# Microcontroller.net
KiCad netlist of a schematic drawn in Altium Designer
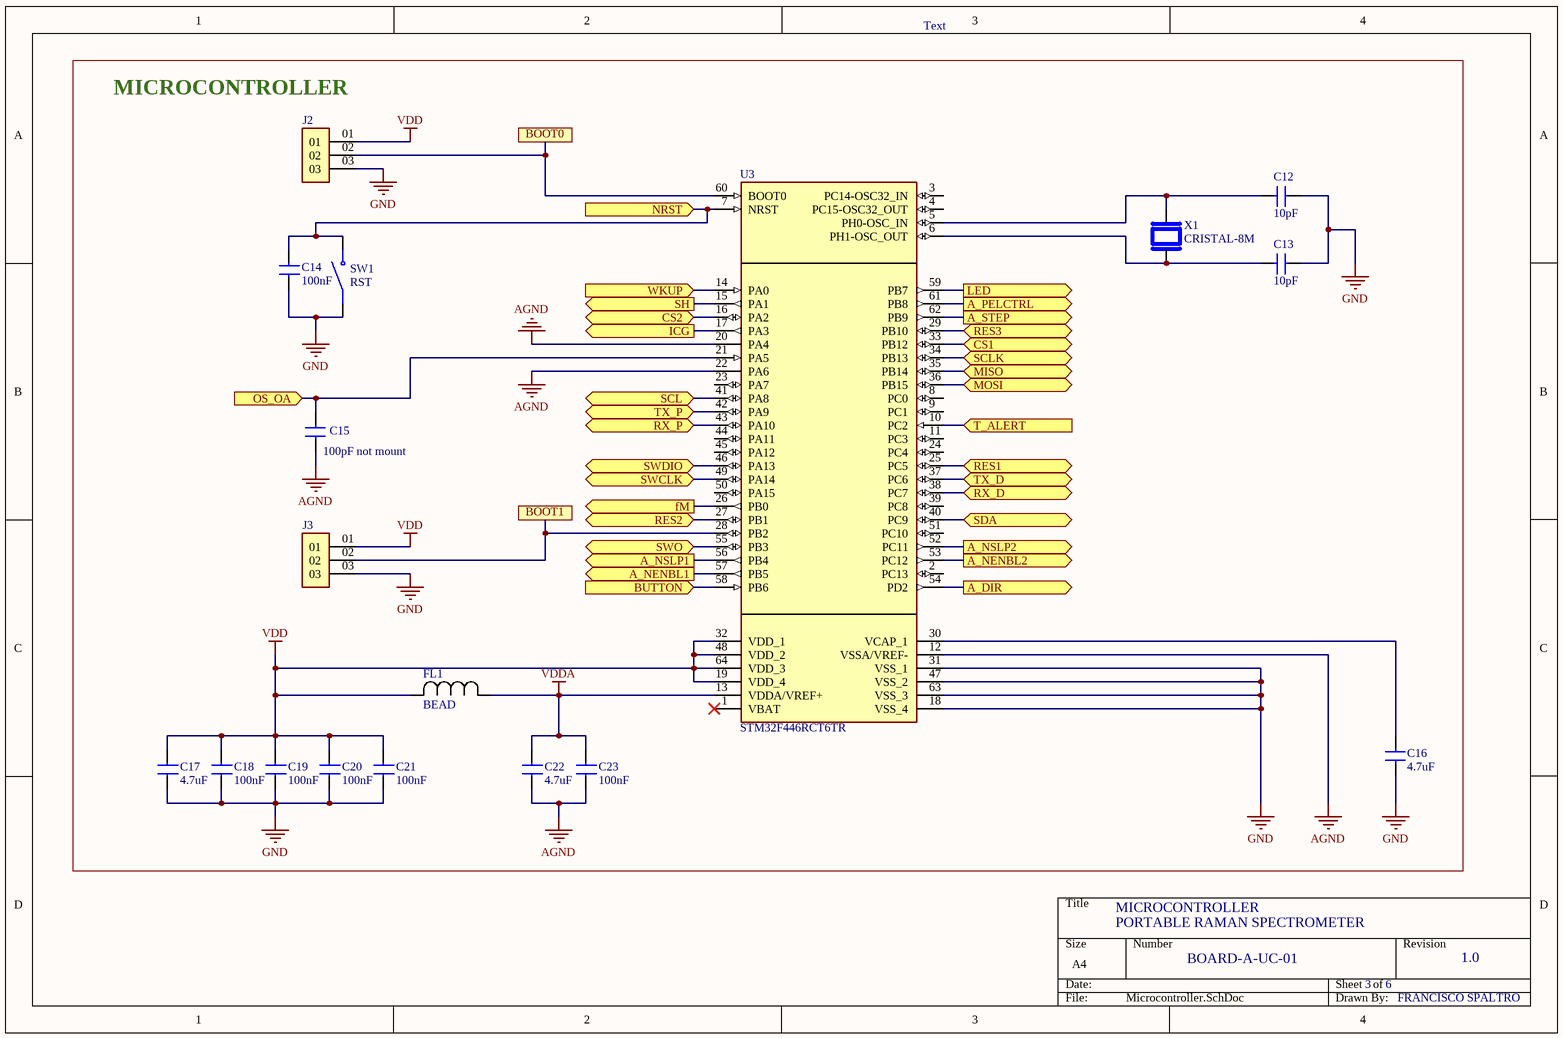
[diagram p0: Microcontroller.SchDoc]

(export (version "E")
  (design (tool "Eeschema 10.0.6"))
  (components
    (comp (ref "C12")
      (value "10pF")
      (footprint "RES_0805")
      (description "Generic Capacitor")
      (libsource (lib "Components") (part "CAP_0805"))
    )
    (comp (ref "C13")
      (value "10pF")
      (footprint "RES_0805")
      (description "Generic Capacitor")
      (libsource (lib "Components") (part "CAP_0805"))
    )
    (comp (ref "C14")
      (value "100nF")
      (footprint "RES_0805")
      (description "Generic Capacitor")
      (libsource (lib "Components") (part "CAP_0805"))
    )
    (comp (ref "C15")
      (value "100pF not mount")
      (footprint "RES_0805")
      (description "Generic Capacitor")
      (libsource (lib "Components") (part "CAP_0805"))
    )
    (comp (ref "C16")
      (value "4.7uF")
      (footprint "RES_0805")
      (description "Generic Capacitor")
      (libsource (lib "Components") (part "CAP_0805"))
    )
    (comp (ref "C17")
      (value "4.7uF")
      (footprint "RES_0805")
      (description "Generic Capacitor")
      (libsource (lib "Components") (part "CAP_0805"))
    )
    (comp (ref "C18")
      (value "100nF")
      (footprint "RES_0805")
      (description "Generic Capacitor")
      (libsource (lib "Components") (part "CAP_0805"))
    )
    (comp (ref "C19")
      (value "100nF")
      (footprint "RES_0805")
      (description "Generic Capacitor")
      (libsource (lib "Components") (part "CAP_0805"))
    )
    (comp (ref "C20")
      (value "100nF")
      (footprint "RES_0805")
      (description "Generic Capacitor")
      (libsource (lib "Components") (part "CAP_0805"))
    )
    (comp (ref "C21")
      (value "100nF")
      (footprint "RES_0805")
      (description "Generic Capacitor")
      (libsource (lib "Components") (part "CAP_0805"))
    )
    (comp (ref "C22")
      (value "4.7uF")
      (footprint "RES_0805")
      (description "Generic Capacitor")
      (libsource (lib "Components") (part "CAP_0805"))
    )
    (comp (ref "C23")
      (value "100nF")
      (footprint "RES_0805")
      (description "Generic Capacitor")
      (libsource (lib "Components") (part "CAP_0805"))
    )
    (comp (ref "FL1")
      (value "BEAD")
      (footprint "IND_1608_TDK-M")
      (description "INDUCTOR; SMT (0603); FERRITE-BEAD; 600; TOL=+/-25%; 0.5A; -55 DEGC TO +125 DEGC")
      (fields
        (field (name "MANUFACTURER_PART_NUMBER") "MMZ1608B601CTAH0")
        (field (name "COPYRIGHT") "Copyright (C) 2025 Ultra Librarian. All rights reserved.")
      )
      (libsource (lib "Components") (part "MMZ1608B601CTAH0"))
    )
    (comp (ref "J2")
      (value "PIN_HEADER_3")
      (footprint "GEN_PIN3")
      (description "Generic 40 mils drill size, 100 mils step")
      (fields (field (name "MF") "Samtec Inc.") (field (name "MP") "TS-103-T-A"))
      (libsource (lib "Components") (part "PIN_HEADER_3"))
    )
    (comp (ref "J3")
      (value "PIN_HEADER_3")
      (footprint "GEN_PIN3")
      (description "Generic 40 mils drill size, 100 mils step")
      (fields (field (name "MF") "Samtec Inc.") (field (name "MP") "TS-103-T-A"))
      (libsource (lib "Components") (part "PIN_HEADER_3"))
    )
    (comp (ref "SW1")
      (value "RST")
      (footprint "Components:SW_B3U-1000P")
      (description "Switch Tactile N.O. SPST Round Button Gull Wing 0.05A 12VDC 1.5N SMD Embossed T/R")
      (fields (field (name "MP") "B3U-1000P"))
      (libsource (lib "Components") (part "SW-B3U-1000P"))
    )
    (comp (ref "U3")
      (value "STM32F446RCT6TR")
      (footprint "QFP50P1200X1200X160-64N")
      (fields (field (name "MF") "STMicroelectronics"))
      (libsource (lib "CI") (part "STM32F446RCT6TR"))
    )
    (comp (ref "X1")
      (value "CRISTAL-8M")
      (footprint "XTALDFN320X250X100-2N")
      (description "8 MHz ±20ppm Crystal 8pF 500 Ohms 2-SMD, No Lead")
      (fields (field (name "MF") "NDK America, Inc.") (field (name "MP") "CG04874-8M"))
      (libsource (lib "CompPas") (part "CRISTAL-CG04874-8M"))
    )
  )
  (nets
    (net (code "1") (name "/A_DIR") (class "Default")
      (node (ref "U3") (pin "54") (pinfunction "PD2_54") (pintype "output"))
    )
    (net (code "2") (name "/A_NENBL1") (class "Default")
      (node (ref "U3") (pin "57") (pinfunction "PB5_57") (pintype "output"))
    )
    (net (code "3") (name "/A_NENBL2") (class "Default")
      (node (ref "U3") (pin "53") (pinfunction "PC12_53") (pintype "output"))
    )
    (net (code "4") (name "/A_NSLP1") (class "Default")
      (node (ref "U3") (pin "56") (pinfunction "PB4_56") (pintype "output"))
    )
    (net (code "5") (name "/A_NSLP2") (class "Default")
      (node (ref "U3") (pin "52") (pinfunction "PC11_52") (pintype "output"))
    )
    (net (code "6") (name "/A_PELCTRL") (class "Default")
      (node (ref "U3") (pin "61") (pinfunction "PB8_61") (pintype "output"))
    )
    (net (code "7") (name "/A_STEP") (class "Default")
      (node (ref "U3") (pin "62") (pinfunction "PB9_62") (pintype "output"))
    )
    (net (code "8") (name "/BOOT0") (class "Default")
      (node (ref "J2") (pin "02") (pinfunction "02_02") (pintype "passive"))
      (node (ref "U3") (pin "60") (pinfunction "BOOT0_60") (pintype "input"))
    )
    (net (code "9") (name "/BOOT1") (class "Default")
      (node (ref "J3") (pin "02") (pinfunction "02_02") (pintype "passive"))
      (node (ref "U3") (pin "28") (pinfunction "PB2_28") (pintype "bidirectional"))
    )
    (net (code "10") (name "/BUTTON") (class "Default")
      (node (ref "U3") (pin "58") (pinfunction "PB6_58") (pintype "input"))
    )
    (net (code "11") (name "/CS1") (class "Default")
      (node (ref "U3") (pin "33") (pinfunction "PB12_33") (pintype "bidirectional"))
    )
    (net (code "12") (name "/CS2") (class "Default")
      (node (ref "U3") (pin "16") (pinfunction "PA2_16") (pintype "bidirectional"))
    )
    (net (code "13") (name "/ICG") (class "Default")
      (node (ref "U3") (pin "17") (pinfunction "PA3_17") (pintype "output"))
    )
    (net (code "14") (name "/LED") (class "Default")
      (node (ref "U3") (pin "59") (pinfunction "PB7_59") (pintype "output"))
    )
    (net (code "15") (name "/MISO") (class "Default")
      (node (ref "U3") (pin "35") (pinfunction "PB14_35") (pintype "bidirectional"))
    )
    (net (code "16") (name "/MOSI") (class "Default")
      (node (ref "U3") (pin "36") (pinfunction "PB15_36") (pintype "bidirectional"))
    )
    (net (code "17") (name "/NRST") (class "Default")
      (node (ref "C14") (pin "1") (pinfunction "1_1") (pintype "passive"))
      (node (ref "SW1") (pin "2") (pinfunction "2_2") (pintype "passive"))
      (node (ref "U3") (pin "7") (pinfunction "NRST_7") (pintype "input"))
    )
    (net (code "18") (name "/OS_OA") (class "Default")
      (node (ref "C15") (pin "2") (pinfunction "2_2") (pintype "passive"))
      (node (ref "U3") (pin "21") (pinfunction "PA5_21") (pintype "input"))
    )
    (net (code "19") (name "/RES1") (class "Default")
      (node (ref "U3") (pin "25") (pinfunction "PC5_25") (pintype "bidirectional"))
    )
    (net (code "20") (name "/RES2") (class "Default")
      (node (ref "U3") (pin "27") (pinfunction "PB1_27") (pintype "bidirectional"))
    )
    (net (code "21") (name "/RES3") (class "Default")
      (node (ref "U3") (pin "29") (pinfunction "PB10_29") (pintype "bidirectional"))
    )
    (net (code "22") (name "/RX_D") (class "Default")
      (node (ref "U3") (pin "38") (pinfunction "PC7_38") (pintype "bidirectional"))
    )
    (net (code "23") (name "/RX_P") (class "Default")
      (node (ref "U3") (pin "43") (pinfunction "PA10_43") (pintype "bidirectional"))
    )
    (net (code "24") (name "/SCL") (class "Default")
      (node (ref "U3") (pin "41") (pinfunction "PA8_41") (pintype "bidirectional"))
    )
    (net (code "25") (name "/SCLK") (class "Default")
      (node (ref "U3") (pin "34") (pinfunction "PB13_34") (pintype "bidirectional"))
    )
    (net (code "26") (name "/SDA") (class "Default")
      (node (ref "U3") (pin "40") (pinfunction "PC9_40") (pintype "bidirectional"))
    )
    (net (code "27") (name "/SH") (class "Default")
      (node (ref "U3") (pin "15") (pinfunction "PA1_15") (pintype "output"))
    )
    (net (code "28") (name "/SWCLK") (class "Default")
      (node (ref "U3") (pin "49") (pinfunction "PA14_49") (pintype "bidirectional"))
    )
    (net (code "29") (name "/SWDIO") (class "Default")
      (node (ref "U3") (pin "46") (pinfunction "PA13_46") (pintype "bidirectional"))
    )
    (net (code "30") (name "/SWO") (class "Default")
      (node (ref "U3") (pin "55") (pinfunction "PB3_55") (pintype "bidirectional"))
    )
    (net (code "31") (name "/TX_D") (class "Default")
      (node (ref "U3") (pin "37") (pinfunction "PC6_37") (pintype "bidirectional"))
    )
    (net (code "32") (name "/TX_P") (class "Default")
      (node (ref "U3") (pin "42") (pinfunction "PA9_42") (pintype "bidirectional"))
    )
    (net (code "33") (name "/T_ALERT") (class "Default")
      (node (ref "U3") (pin "10") (pinfunction "PC2_10") (pintype "input"))
    )
    (net (code "34") (name "/WKUP") (class "Default")
      (node (ref "U3") (pin "14") (pinfunction "PA0_14") (pintype "input"))
    )
    (net (code "35") (name "/fM") (class "Default")
      (node (ref "U3") (pin "26") (pinfunction "PB0_26") (pintype "output"))
    )
    (net (code "36") (name "AGND") (class "Default")
      (node (ref "C15") (pin "1") (pinfunction "1_1") (pintype "passive"))
      (node (ref "C22") (pin "2") (pinfunction "2_2") (pintype "passive"))
      (node (ref "C23") (pin "2") (pinfunction "2_2") (pintype "passive"))
      (node (ref "U3") (pin "12") (pinfunction "VSSA/VREF-_12") (pintype "passive"))
      (node (ref "U3") (pin "20") (pinfunction "PA4_20") (pintype "passive"))
      (node (ref "U3") (pin "22") (pinfunction "PA6_22") (pintype "passive"))
    )
    (net (code "37") (name "GND") (class "Default")
      (node (ref "C12") (pin "1") (pinfunction "1_1") (pintype "passive"))
      (node (ref "C13") (pin "1") (pinfunction "1_1") (pintype "passive"))
      (node (ref "C14") (pin "2") (pinfunction "2_2") (pintype "passive"))
      (node (ref "C16") (pin "1") (pinfunction "1_1") (pintype "passive"))
      (node (ref "C17") (pin "2") (pinfunction "2_2") (pintype "passive"))
      (node (ref "C18") (pin "2") (pinfunction "2_2") (pintype "passive"))
      (node (ref "C19") (pin "2") (pinfunction "2_2") (pintype "passive"))
      (node (ref "C20") (pin "2") (pinfunction "2_2") (pintype "passive"))
      (node (ref "C21") (pin "2") (pinfunction "2_2") (pintype "passive"))
      (node (ref "J2") (pin "03") (pinfunction "03_03") (pintype "passive"))
      (node (ref "J3") (pin "03") (pinfunction "03_03") (pintype "passive"))
      (node (ref "SW1") (pin "1") (pinfunction "1_1") (pintype "passive"))
      (node (ref "U3") (pin "18") (pinfunction "VSS_4_18") (pintype "power_in"))
      (node (ref "U3") (pin "31") (pinfunction "VSS_1_31") (pintype "power_in"))
      (node (ref "U3") (pin "47") (pinfunction "VSS_2_47") (pintype "power_in"))
      (node (ref "U3") (pin "63") (pinfunction "VSS_3_63") (pintype "power_in"))
    )
    (net (code "38") (name "Net-(U3-PH0-OSC_IN)") (class "Default")
      (node (ref "C12") (pin "2") (pinfunction "2_2") (pintype "passive"))
      (node (ref "U3") (pin "5") (pinfunction "PH0-OSC_IN_5") (pintype "bidirectional"))
      (node (ref "X1") (pin "2") (pinfunction "2_2") (pintype "passive"))
    )
    (net (code "39") (name "Net-(U3-PH1-OSC_OUT)") (class "Default")
      (node (ref "C13") (pin "2") (pinfunction "2_2") (pintype "passive"))
      (node (ref "U3") (pin "6") (pinfunction "PH1-OSC_OUT_6") (pintype "bidirectional"))
      (node (ref "X1") (pin "1") (pinfunction "1_1") (pintype "passive"))
    )
    (net (code "40") (name "Net-(U3-VCAP_1)") (class "Default")
      (node (ref "C16") (pin "2") (pinfunction "2_2") (pintype "passive"))
      (node (ref "U3") (pin "30") (pinfunction "VCAP_1_30") (pintype "power_in"))
    )
    (net (code "41") (name "VDD") (class "Default")
      (node (ref "C17") (pin "1") (pinfunction "1_1") (pintype "passive"))
      (node (ref "C18") (pin "1") (pinfunction "1_1") (pintype "passive"))
      (node (ref "C19") (pin "1") (pinfunction "1_1") (pintype "passive"))
      (node (ref "C20") (pin "1") (pinfunction "1_1") (pintype "passive"))
      (node (ref "C21") (pin "1") (pinfunction "1_1") (pintype "passive"))
      (node (ref "FL1") (pin "2") (pinfunction "2_2") (pintype "passive"))
      (node (ref "J2") (pin "01") (pinfunction "01_01") (pintype "passive"))
      (node (ref "J3") (pin "01") (pinfunction "01_01") (pintype "passive"))
      (node (ref "U3") (pin "19") (pinfunction "VDD_4_19") (pintype "power_in"))
      (node (ref "U3") (pin "32") (pinfunction "VDD_1_32") (pintype "power_in"))
      (node (ref "U3") (pin "48") (pinfunction "VDD_2_48") (pintype "power_in"))
      (node (ref "U3") (pin "64") (pinfunction "VDD_3_64") (pintype "power_in"))
    )
    (net (code "42") (name "VDDA") (class "Default")
      (node (ref "C22") (pin "1") (pinfunction "1_1") (pintype "passive"))
      (node (ref "C23") (pin "1") (pinfunction "1_1") (pintype "passive"))
      (node (ref "FL1") (pin "1") (pinfunction "1_1") (pintype "passive"))
      (node (ref "U3") (pin "13") (pinfunction "VDDA/VREF+_13") (pintype "power_in"))
    )
    (net (code "43") (name "unconnected-(U3-PA7-Pad23)") (class "Default")
      (node (ref "U3") (pin "23") (pinfunction "PA7_23") (pintype "bidirectional"))
    )
    (net (code "44") (name "unconnected-(U3-PA11-Pad44)") (class "Default")
      (node (ref "U3") (pin "44") (pinfunction "PA11_44") (pintype "bidirectional"))
    )
    (net (code "45") (name "unconnected-(U3-PA12-Pad45)") (class "Default")
      (node (ref "U3") (pin "45") (pinfunction "PA12_45") (pintype "bidirectional"))
    )
    (net (code "46") (name "unconnected-(U3-PA15-Pad50)") (class "Default")
      (node (ref "U3") (pin "50") (pinfunction "PA15_50") (pintype "bidirectional"))
    )
    (net (code "47") (name "unconnected-(U3-PC0-Pad8)") (class "Default")
      (node (ref "U3") (pin "8") (pinfunction "PC0_8") (pintype "bidirectional"))
    )
    (net (code "48") (name "unconnected-(U3-PC1-Pad9)") (class "Default")
      (node (ref "U3") (pin "9") (pinfunction "PC1_9") (pintype "bidirectional"))
    )
    (net (code "49") (name "unconnected-(U3-PC3-Pad11)") (class "Default")
      (node (ref "U3") (pin "11") (pinfunction "PC3_11") (pintype "bidirectional"))
    )
    (net (code "50") (name "unconnected-(U3-PC4-Pad24)") (class "Default")
      (node (ref "U3") (pin "24") (pinfunction "PC4_24") (pintype "bidirectional"))
    )
    (net (code "51") (name "unconnected-(U3-PC8-Pad39)") (class "Default")
      (node (ref "U3") (pin "39") (pinfunction "PC8_39") (pintype "bidirectional"))
    )
    (net (code "52") (name "unconnected-(U3-PC10-Pad51)") (class "Default")
      (node (ref "U3") (pin "51") (pinfunction "PC10_51") (pintype "bidirectional"))
    )
    (net (code "53") (name "unconnected-(U3-PC13-Pad2)") (class "Default")
      (node (ref "U3") (pin "2") (pinfunction "PC13_2") (pintype "bidirectional"))
    )
    (net (code "54") (name "unconnected-(U3-PC14-OSC32_IN-Pad3)") (class "Default")
      (node (ref "U3") (pin "3") (pinfunction "PC14-OSC32_IN_3") (pintype "bidirectional"))
    )
    (net (code "55") (name "unconnected-(U3-PC15-OSC32_OUT-Pad4)") (class "Default")
      (node (ref "U3") (pin "4") (pinfunction "PC15-OSC32_OUT_4") (pintype "bidirectional"))
    )
    (net (code "56") (name "unconnected-(U3-VBAT-Pad1)") (class "Default")
      (node (ref "U3") (pin "1") (pinfunction "VBAT_1") (pintype "power_in+no_connect"))
    )
  )
)
